# Funkcijski_generator_sema.net
KiCad netlist of a schematic drawn in Altium Designer
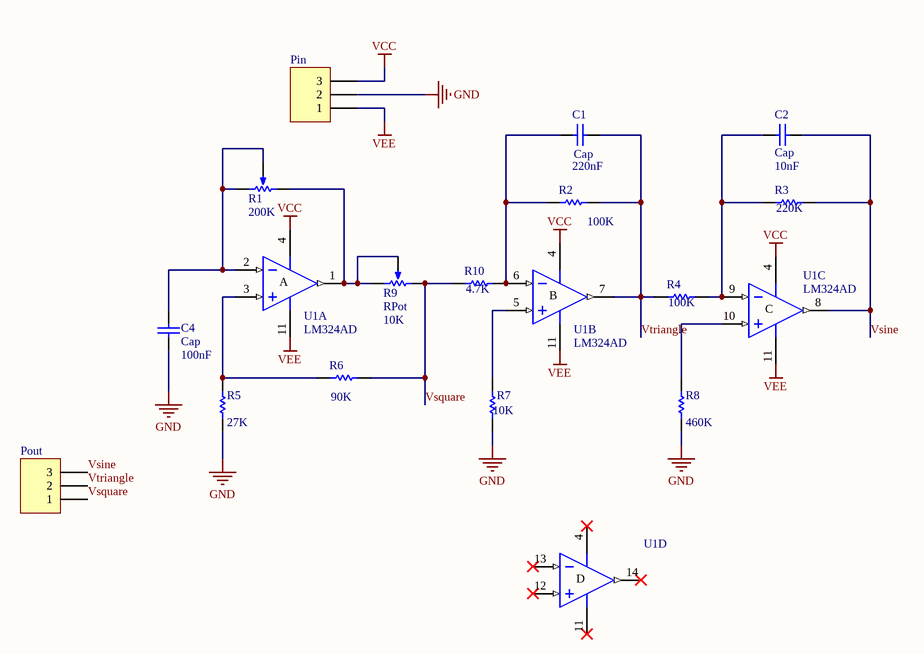
[diagram p0: Funkcijski_generator_sema.SchDoc]

(export (version "E")
  (design (tool "Eeschema 10.0.6"))
  (components
    (comp (ref "C1")
      (value "Cap")
      (footprint "RAD-0.3")
      (description "Capacitor")
      (fields (field (name "ALTIUM_VALUE") "220nF") (field (name "PUBLISHER") "Altium Limited"))
      (libsource (lib "Miscellaneous Devices") (part "Cap"))
    )
    (comp (ref "C2")
      (value "Cap")
      (footprint "RAD-0.3")
      (description "Capacitor")
      (fields (field (name "ALTIUM_VALUE") "10nF") (field (name "PUBLISHER") "Altium Limited"))
      (libsource (lib "Miscellaneous Devices") (part "Cap"))
    )
    (comp (ref "C4")
      (value "Cap")
      (footprint "RAD-0.3")
      (description "Capacitor")
      (fields (field (name "ALTIUM_VALUE") "100nF") (field (name "PUBLISHER") "Altium Limited"))
      (libsource (lib "Miscellaneous Devices") (part "Cap"))
    )
    (comp (ref "Pin")
      (value "Header 3")
      (footprint "HDR1X3")
      (description "Header, 3-Pin")
      (fields (field (name "PUBLISHER") "Altium Limited"))
      (libsource (lib "Miscellaneous Connectors") (part "Header 3"))
    )
    (comp (ref "Pout")
      (value "Header 3")
      (footprint "HDR1X3")
      (description "Header, 3-Pin")
      (fields (field (name "PUBLISHER") "Altium Limited"))
      (libsource (lib "Miscellaneous Connectors") (part "Header 3"))
    )
    (comp (ref "R1")
      (value "200K")
      (footprint "VR5")
      (description "Potentiometer")
      (fields (field (name "Comment") "RPot") (field (name "PUBLISHER") "Altium Limited"))
      (libsource (lib "Miscellaneous Devices") (part "RPot"))
    )
    (comp (ref "R2")
      (value "100K")
      (footprint "AXIAL-0.3")
      (description "Resistor")
      (fields (field (name "Comment") "Res1") (field (name "PUBLISHER") "Altium Limited"))
      (libsource (lib "Miscellaneous Devices") (part "Res1"))
    )
    (comp (ref "R3")
      (value "220K")
      (footprint "AXIAL-0.3")
      (description "Resistor")
      (fields (field (name "Comment") "Res1") (field (name "PUBLISHER") "Altium Limited"))
      (libsource (lib "Miscellaneous Devices") (part "Res1"))
    )
    (comp (ref "R4")
      (value "100K")
      (footprint "AXIAL-0.3")
      (description "Resistor")
      (fields (field (name "Comment") "Res1") (field (name "PUBLISHER") "Altium Limited"))
      (libsource (lib "Miscellaneous Devices") (part "Res1"))
    )
    (comp (ref "R5")
      (value "27K")
      (footprint "AXIAL-0.3")
      (description "Resistor")
      (fields (field (name "Comment") "Res1") (field (name "PUBLISHER") "Altium Limited"))
      (libsource (lib "Miscellaneous Devices") (part "Res1"))
    )
    (comp (ref "R6")
      (value "90K")
      (footprint "AXIAL-0.3")
      (description "Resistor")
      (fields (field (name "Comment") "Res1") (field (name "PUBLISHER") "Altium Limited"))
      (libsource (lib "Miscellaneous Devices") (part "Res1"))
    )
    (comp (ref "R7")
      (value "10K")
      (footprint "AXIAL-0.3")
      (description "Resistor")
      (fields (field (name "Comment") "Res1") (field (name "PUBLISHER") "Altium Limited"))
      (libsource (lib "Miscellaneous Devices") (part "Res1"))
    )
    (comp (ref "R8")
      (value "460K")
      (footprint "AXIAL-0.3")
      (description "Resistor")
      (fields (field (name "Comment") "Res1") (field (name "PUBLISHER") "Altium Limited"))
      (libsource (lib "Miscellaneous Devices") (part "Res1"))
    )
    (comp (ref "R9")
      (value "RPot")
      (footprint "VR5")
      (description "Potentiometer")
      (fields (field (name "ALTIUM_VALUE") "10K") (field (name "PUBLISHER") "Altium Limited"))
      (libsource (lib "Miscellaneous Devices") (part "RPot"))
    )
    (comp (ref "R10")
      (value "4.7K")
      (footprint "AXIAL-0.3")
      (description "Resistor")
      (fields (field (name "Comment") "Res1") (field (name "PUBLISHER") "Altium Limited"))
      (libsource (lib "Miscellaneous Devices") (part "Res1"))
    )
    (comp (ref "U1")
      (value "LM324AD")
      (footprint "DIP-14")
      (description "Low-Power Quad Operational Amplifier")
      (fields (field (name "PUBLISHER") "Altium Limited"))
      (libsource (lib "ST Operational Amplifier") (part "LM324AD"))
    )
  )
  (nets
    (net (code "1") (name "/Vsine") (class "Default")
      (node (ref "C2") (pin "1") (pinfunction "1_1") (pintype "passive"))
      (node (ref "Pout") (pin "3") (pinfunction "3_3") (pintype "passive"))
      (node (ref "R3") (pin "2") (pinfunction "2_2") (pintype "passive"))
      (node (ref "U1") (pin "8") (pinfunction "OUT_8") (pintype "output"))
    )
    (net (code "2") (name "/Vsquare") (class "Default")
      (node (ref "Pout") (pin "1") (pinfunction "1_1") (pintype "passive"))
      (node (ref "R10") (pin "1") (pinfunction "1_1") (pintype "passive"))
      (node (ref "R6") (pin "2") (pinfunction "2_2") (pintype "passive"))
      (node (ref "R9") (pin "1") (pinfunction "TOP_1") (pintype "passive"))
    )
    (net (code "3") (name "/Vtriangle") (class "Default")
      (node (ref "C1") (pin "1") (pinfunction "1_1") (pintype "passive"))
      (node (ref "Pout") (pin "2") (pinfunction "2_2") (pintype "passive"))
      (node (ref "R2") (pin "2") (pinfunction "2_2") (pintype "passive"))
      (node (ref "R4") (pin "1") (pinfunction "1_1") (pintype "passive"))
      (node (ref "U1") (pin "7") (pinfunction "OUT_7") (pintype "output"))
    )
    (net (code "4") (name "GND") (class "Default")
      (node (ref "C4") (pin "1") (pinfunction "1_1") (pintype "passive"))
      (node (ref "Pin") (pin "2") (pinfunction "2_2") (pintype "passive"))
      (node (ref "R5") (pin "1") (pinfunction "1_1") (pintype "passive"))
      (node (ref "R7") (pin "1") (pinfunction "1_1") (pintype "passive"))
      (node (ref "R8") (pin "1") (pinfunction "1_1") (pintype "passive"))
    )
    (net (code "5") (name "Net-(R1-BOT)") (class "Default")
      (node (ref "C4") (pin "2") (pinfunction "2_2") (pintype "passive"))
      (node (ref "R1") (pin "2") (pinfunction "BOT_2") (pintype "passive"))
      (node (ref "R1") (pin "3") (pinfunction "TAP_3") (pintype "passive"))
      (node (ref "U1") (pin "2") (pinfunction "IN-_2") (pintype "input"))
    )
    (net (code "6") (name "Net-(R1-TOP)") (class "Default")
      (node (ref "R1") (pin "1") (pinfunction "TOP_1") (pintype "passive"))
      (node (ref "R9") (pin "2") (pinfunction "BOT_2") (pintype "passive"))
      (node (ref "R9") (pin "3") (pinfunction "TAP_3") (pintype "passive"))
      (node (ref "U1") (pin "1") (pinfunction "OUT_1") (pintype "output"))
    )
    (net (code "7") (name "Net-(U1A-IN+)") (class "Default")
      (node (ref "R5") (pin "2") (pinfunction "2_2") (pintype "passive"))
      (node (ref "R6") (pin "1") (pinfunction "1_1") (pintype "passive"))
      (node (ref "U1") (pin "3") (pinfunction "IN+_3") (pintype "input"))
    )
    (net (code "8") (name "Net-(U1B-IN+)") (class "Default")
      (node (ref "R7") (pin "2") (pinfunction "2_2") (pintype "passive"))
      (node (ref "U1") (pin "5") (pinfunction "IN+_5") (pintype "input"))
    )
    (net (code "9") (name "Net-(U1B-IN-)") (class "Default")
      (node (ref "C1") (pin "2") (pinfunction "2_2") (pintype "passive"))
      (node (ref "R10") (pin "2") (pinfunction "2_2") (pintype "passive"))
      (node (ref "R2") (pin "1") (pinfunction "1_1") (pintype "passive"))
      (node (ref "U1") (pin "6") (pinfunction "IN-_6") (pintype "input"))
    )
    (net (code "10") (name "Net-(U1C-IN+)") (class "Default")
      (node (ref "R8") (pin "2") (pinfunction "2_2") (pintype "passive"))
      (node (ref "U1") (pin "10") (pinfunction "IN+_10") (pintype "input"))
    )
    (net (code "11") (name "Net-(U1C-IN-)") (class "Default")
      (node (ref "C2") (pin "2") (pinfunction "2_2") (pintype "passive"))
      (node (ref "R3") (pin "1") (pinfunction "1_1") (pintype "passive"))
      (node (ref "R4") (pin "2") (pinfunction "2_2") (pintype "passive"))
      (node (ref "U1") (pin "9") (pinfunction "IN-_9") (pintype "input"))
    )
    (net (code "12") (name "VCC") (class "Default")
      (node (ref "Pin") (pin "3") (pinfunction "3_3") (pintype "passive"))
      (node (ref "U1") (pin "4") (pinfunction "V+_4") (pintype "power_in"))
    )
    (net (code "13") (name "VEE") (class "Default")
      (node (ref "Pin") (pin "1") (pinfunction "1_1") (pintype "passive"))
      (node (ref "U1") (pin "11") (pinfunction "V-_11") (pintype "power_in"))
    )
    (net (code "14") (name "unconnected-(U1D-IN+-Pad12)") (class "Default")
      (node (ref "U1") (pin "12") (pinfunction "IN+_12") (pintype "input+no_connect"))
    )
    (net (code "15") (name "unconnected-(U1D-IN--Pad13)") (class "Default")
      (node (ref "U1") (pin "13") (pinfunction "IN-_13") (pintype "input+no_connect"))
    )
    (net (code "16") (name "unconnected-(U1D-OUT-Pad14)") (class "Default")
      (node (ref "U1") (pin "14") (pinfunction "OUT_14") (pintype "output+no_connect"))
    )
    (net (code "17") (name "unconnected-(U1D-V+-Pad4)") (class "Default")
      (node (ref "U1") (pin "4") (pinfunction "V+_4") (pintype "power_in+no_connect"))
    )
    (net (code "18") (name "unconnected-(U1D-V--Pad11)") (class "Default")
      (node (ref "U1") (pin "11") (pinfunction "V-_11") (pintype "power_in+no_connect"))
    )
  )
)
